# but8LED.net
KiCad netlist of a schematic drawn in EAGLE
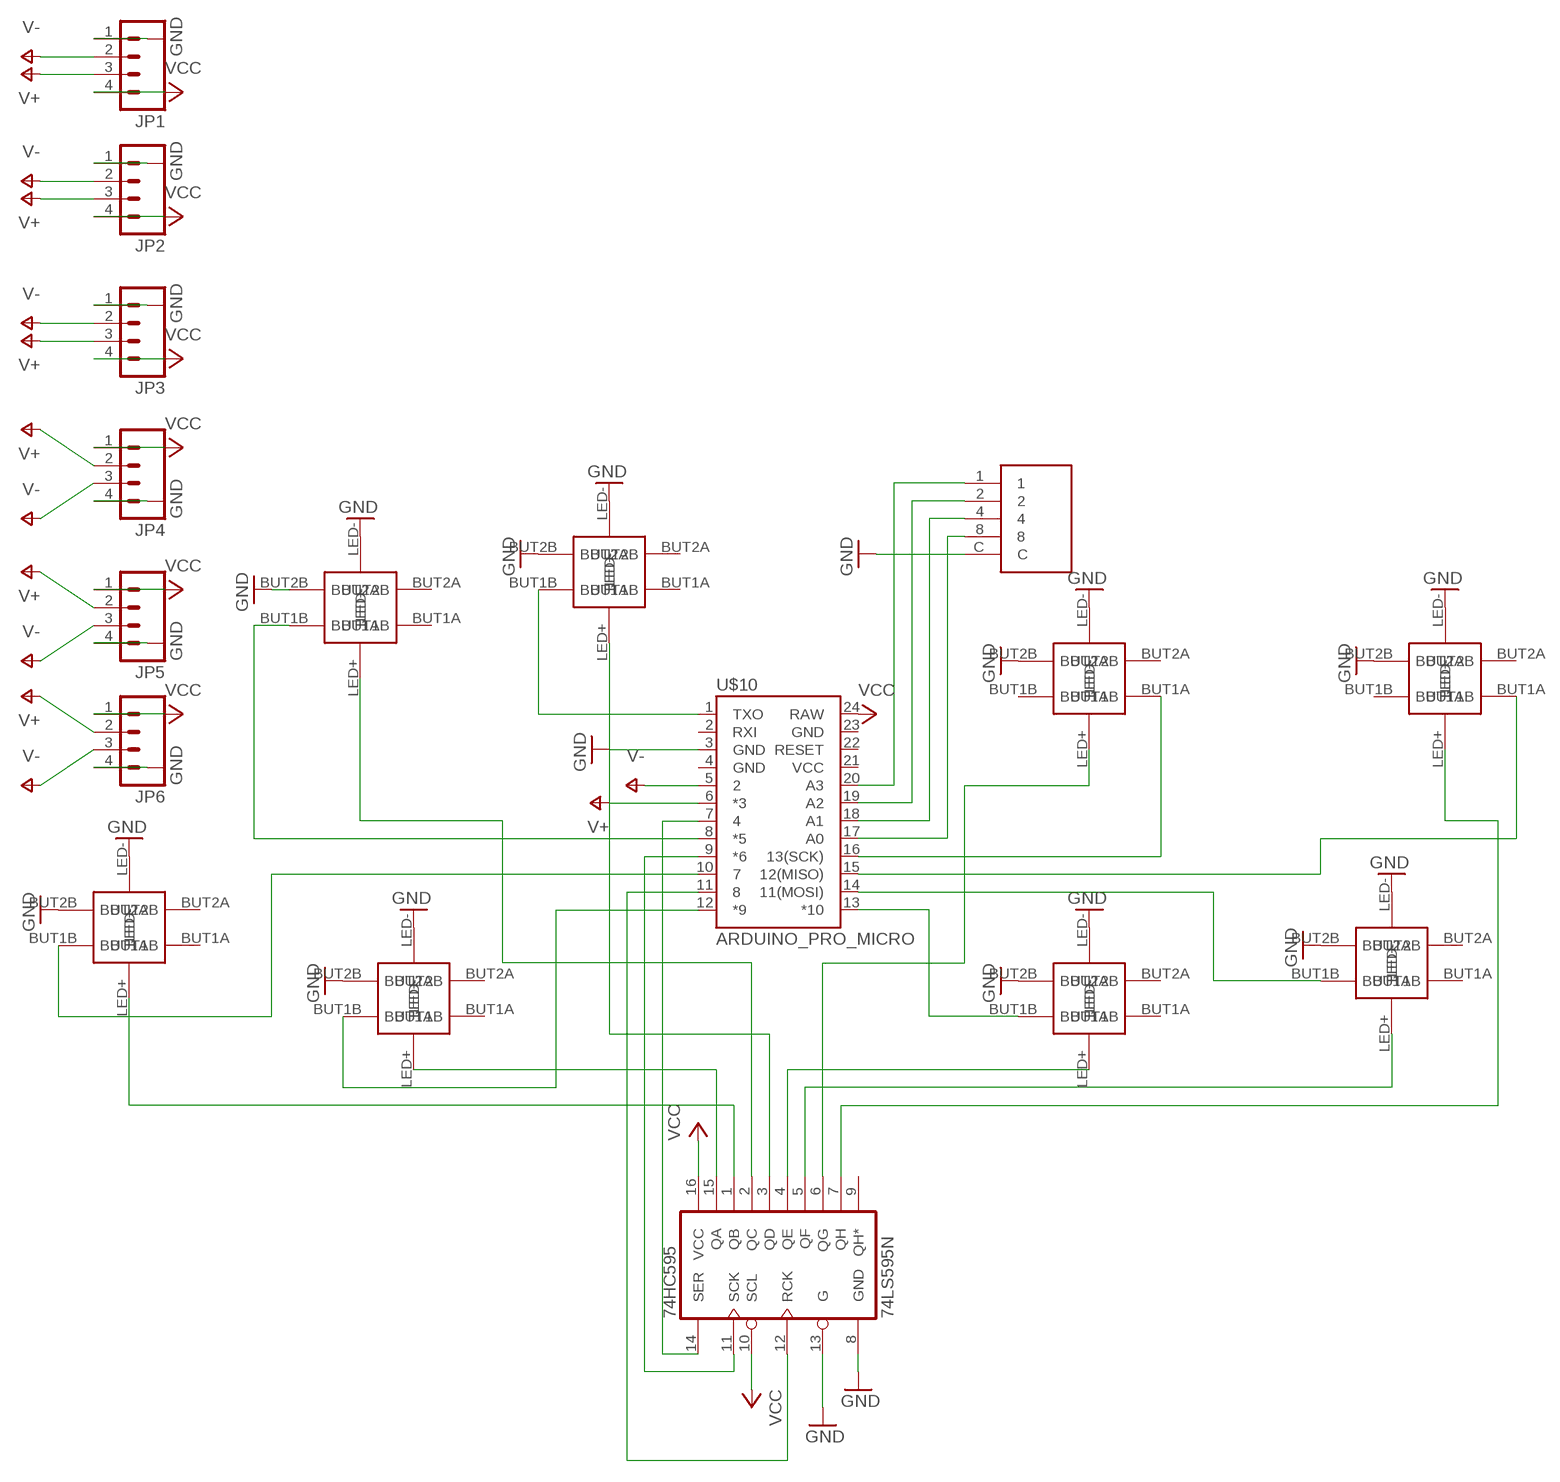
[diagram p0: schematic, sheet 1]

(export (version "E")
  (design (tool "Eeschema 10.0.6"))
  (components
    (comp (ref "74HC595")
      (value "74LS595N")
      (footprint "eagle-import:DIL16")
      (libsource (lib "eagle-import") (part "74595NLS"))
    )
    (comp (ref "JP1")
      (value "M04PTH")
      (footprint "eagle-import:1X04")
      (libsource (lib "eagle-import") (part "M04PTH"))
    )
    (comp (ref "JP2")
      (value "M04PTH")
      (footprint "eagle-import:1X04")
      (libsource (lib "eagle-import") (part "M04PTH"))
    )
    (comp (ref "JP3")
      (value "M04PTH")
      (footprint "eagle-import:1X04")
      (libsource (lib "eagle-import") (part "M04PTH"))
    )
    (comp (ref "JP4")
      (value "M04PTH")
      (footprint "eagle-import:1X04")
      (libsource (lib "eagle-import") (part "M04PTH"))
    )
    (comp (ref "JP5")
      (value "M04PTH")
      (footprint "eagle-import:1X04")
      (libsource (lib "eagle-import") (part "M04PTH"))
    )
    (comp (ref "JP6")
      (value "M04PTH")
      (footprint "eagle-import:1X04")
      (libsource (lib "eagle-import") (part "M04PTH"))
    )
    (comp (ref "U$1")
      (value "BUTLED")
      (footprint "eagle-import:LEDBUT")
      (libsource (lib "eagle-import") (part "BUTLED"))
    )
    (comp (ref "U$2")
      (value "BUTLED")
      (footprint "eagle-import:LEDBUT")
      (libsource (lib "eagle-import") (part "BUTLED"))
    )
    (comp (ref "U$3")
      (value "BUTLED")
      (footprint "eagle-import:LEDBUT")
      (libsource (lib "eagle-import") (part "BUTLED"))
    )
    (comp (ref "U$4")
      (value "BUTLED")
      (footprint "eagle-import:LEDBUT")
      (libsource (lib "eagle-import") (part "BUTLED"))
    )
    (comp (ref "U$5")
      (value "BUTLED")
      (footprint "eagle-import:LEDBUT")
      (libsource (lib "eagle-import") (part "BUTLED"))
    )
    (comp (ref "U$6")
      (value "BUTLED")
      (footprint "eagle-import:LEDBUT")
      (libsource (lib "eagle-import") (part "BUTLED"))
    )
    (comp (ref "U$7")
      (value "BUTLED")
      (footprint "eagle-import:LEDBUT")
      (libsource (lib "eagle-import") (part "BUTLED"))
    )
    (comp (ref "U$8")
      (value "BUTLED")
      (footprint "eagle-import:LEDBUT")
      (libsource (lib "eagle-import") (part "BUTLED"))
    )
    (comp (ref "U$9")
      (value "SWITCH16POS")
      (footprint "eagle-import:SWITCH16POS")
      (libsource (lib "eagle-import") (part "SWITCH16POS"))
    )
    (comp (ref "U$10")
      (value "ARDUINO_PRO_MICRO")
      (footprint "eagle-import:ARDUINO_PRO_MICRO")
      (libsource (lib "eagle-import") (part "ARDUINO_PRO_MICRO"))
    )
  )
  (nets
    (net (code "1") (name "GND") (class "Default")
      (node (ref "74HC595") (pin "13") (pinfunction "G_13") (pintype "input"))
      (node (ref "74HC595") (pin "8") (pinfunction "GND_8") (pintype "power_in"))
      (node (ref "JP1") (pin "1") (pinfunction "1_1") (pintype "passive"))
      (node (ref "JP2") (pin "1") (pinfunction "1_1") (pintype "passive"))
      (node (ref "JP3") (pin "1") (pinfunction "1_1") (pintype "passive"))
      (node (ref "JP4") (pin "4") (pinfunction "4_4") (pintype "passive"))
      (node (ref "JP5") (pin "4") (pinfunction "4_4") (pintype "passive"))
      (node (ref "JP6") (pin "4") (pinfunction "4_4") (pintype "passive"))
      (node (ref "U$1") (pin "BUT2B") (pinfunction "BUT2B_BUT2B") (pintype "bidirectional"))
      (node (ref "U$1") (pin "LED-") (pinfunction "LED-_LED-") (pintype "bidirectional"))
      (node (ref "U$10") (pin "3") (pinfunction "GND_3") (pintype "bidirectional"))
      (node (ref "U$2") (pin "BUT2B") (pinfunction "BUT2B_BUT2B") (pintype "bidirectional"))
      (node (ref "U$2") (pin "LED-") (pinfunction "LED-_LED-") (pintype "bidirectional"))
      (node (ref "U$3") (pin "BUT2B") (pinfunction "BUT2B_BUT2B") (pintype "bidirectional"))
      (node (ref "U$3") (pin "LED-") (pinfunction "LED-_LED-") (pintype "bidirectional"))
      (node (ref "U$4") (pin "BUT2B") (pinfunction "BUT2B_BUT2B") (pintype "bidirectional"))
      (node (ref "U$4") (pin "LED-") (pinfunction "LED-_LED-") (pintype "bidirectional"))
      (node (ref "U$5") (pin "BUT2B") (pinfunction "BUT2B_BUT2B") (pintype "bidirectional"))
      (node (ref "U$5") (pin "LED-") (pinfunction "LED-_LED-") (pintype "bidirectional"))
      (node (ref "U$6") (pin "BUT2B") (pinfunction "BUT2B_BUT2B") (pintype "bidirectional"))
      (node (ref "U$6") (pin "LED-") (pinfunction "LED-_LED-") (pintype "bidirectional"))
      (node (ref "U$7") (pin "BUT2B") (pinfunction "BUT2B_BUT2B") (pintype "bidirectional"))
      (node (ref "U$7") (pin "LED-") (pinfunction "LED-_LED-") (pintype "bidirectional"))
      (node (ref "U$8") (pin "BUT2B") (pinfunction "BUT2B_BUT2B") (pintype "bidirectional"))
      (node (ref "U$8") (pin "LED-") (pinfunction "LED-_LED-") (pintype "bidirectional"))
      (node (ref "U$9") (pin "C") (pinfunction "C_C") (pintype "bidirectional"))
    )
    (net (code "2") (name "Net-(74HC595-QA)") (class "Default")
      (node (ref "74HC595") (pin "15") (pinfunction "QA_15") (pintype "tri_state"))
      (node (ref "U$5") (pin "LED+") (pinfunction "LED+_LED+") (pintype "bidirectional"))
    )
    (net (code "3") (name "Net-(74HC595-QB)") (class "Default")
      (node (ref "74HC595") (pin "1") (pinfunction "QB_1") (pintype "tri_state"))
      (node (ref "U$6") (pin "LED+") (pinfunction "LED+_LED+") (pintype "bidirectional"))
    )
    (net (code "4") (name "Net-(74HC595-QC)") (class "Default")
      (node (ref "74HC595") (pin "2") (pinfunction "QC_2") (pintype "tri_state"))
      (node (ref "U$1") (pin "LED+") (pinfunction "LED+_LED+") (pintype "bidirectional"))
    )
    (net (code "5") (name "Net-(74HC595-QD)") (class "Default")
      (node (ref "74HC595") (pin "3") (pinfunction "QD_3") (pintype "tri_state"))
      (node (ref "U$2") (pin "LED+") (pinfunction "LED+_LED+") (pintype "bidirectional"))
    )
    (net (code "6") (name "Net-(74HC595-QE)") (class "Default")
      (node (ref "74HC595") (pin "4") (pinfunction "QE_4") (pintype "tri_state"))
      (node (ref "U$7") (pin "LED+") (pinfunction "LED+_LED+") (pintype "bidirectional"))
    )
    (net (code "7") (name "Net-(74HC595-QF)") (class "Default")
      (node (ref "74HC595") (pin "5") (pinfunction "QF_5") (pintype "tri_state"))
      (node (ref "U$8") (pin "LED+") (pinfunction "LED+_LED+") (pintype "bidirectional"))
    )
    (net (code "8") (name "Net-(74HC595-QG)") (class "Default")
      (node (ref "74HC595") (pin "6") (pinfunction "QG_6") (pintype "tri_state"))
      (node (ref "U$3") (pin "LED+") (pinfunction "LED+_LED+") (pintype "bidirectional"))
    )
    (net (code "9") (name "Net-(74HC595-QH)") (class "Default")
      (node (ref "74HC595") (pin "7") (pinfunction "QH_7") (pintype "tri_state"))
      (node (ref "U$4") (pin "LED+") (pinfunction "LED+_LED+") (pintype "bidirectional"))
    )
    (net (code "10") (name "Net-(74HC595-RCK)") (class "Default")
      (node (ref "74HC595") (pin "12") (pinfunction "RCK_12") (pintype "input"))
      (node (ref "U$10") (pin "11") (pinfunction "8_11") (pintype "bidirectional"))
    )
    (net (code "11") (name "Net-(74HC595-SCK)") (class "Default")
      (node (ref "74HC595") (pin "11") (pinfunction "SCK_11") (pintype "input"))
      (node (ref "U$10") (pin "9") (pinfunction "*6_9") (pintype "bidirectional"))
    )
    (net (code "12") (name "Net-(74HC595-SER)") (class "Default")
      (node (ref "74HC595") (pin "14") (pinfunction "SER_14") (pintype "input"))
      (node (ref "U$10") (pin "7") (pinfunction "4_7") (pintype "bidirectional"))
    )
    (net (code "13") (name "Net-(U$10-*5)") (class "Default")
      (node (ref "U$1") (pin "BUT1B") (pinfunction "BUT1B_BUT1B") (pintype "bidirectional"))
      (node (ref "U$10") (pin "8") (pinfunction "*5_8") (pintype "bidirectional"))
    )
    (net (code "14") (name "Net-(U$10-*9)") (class "Default")
      (node (ref "U$10") (pin "12") (pinfunction "*9_12") (pintype "bidirectional"))
      (node (ref "U$5") (pin "BUT1B") (pinfunction "BUT1B_BUT1B") (pintype "bidirectional"))
    )
    (net (code "15") (name "Net-(U$10-*10)") (class "Default")
      (node (ref "U$10") (pin "13") (pinfunction "*10_13") (pintype "bidirectional"))
      (node (ref "U$7") (pin "BUT1B") (pinfunction "BUT1B_BUT1B") (pintype "bidirectional"))
    )
    (net (code "16") (name "Net-(U$10-7)") (class "Default")
      (node (ref "U$10") (pin "10") (pinfunction "7_10") (pintype "bidirectional"))
      (node (ref "U$6") (pin "BUT1B") (pinfunction "BUT1B_BUT1B") (pintype "bidirectional"))
    )
    (net (code "17") (name "Net-(U$10-11(MOSI))") (class "Default")
      (node (ref "U$10") (pin "14") (pinfunction "11(MOSI)_14") (pintype "bidirectional"))
      (node (ref "U$8") (pin "BUT1B") (pinfunction "BUT1B_BUT1B") (pintype "bidirectional"))
    )
    (net (code "18") (name "Net-(U$10-12(MISO))") (class "Default")
      (node (ref "U$10") (pin "15") (pinfunction "12(MISO)_15") (pintype "bidirectional"))
      (node (ref "U$4") (pin "BUT1A") (pinfunction "BUT1A_BUT1A") (pintype "bidirectional"))
    )
    (net (code "19") (name "Net-(U$10-13(SCK))") (class "Default")
      (node (ref "U$10") (pin "16") (pinfunction "13(SCK)_16") (pintype "bidirectional"))
      (node (ref "U$3") (pin "BUT1A") (pinfunction "BUT1A_BUT1A") (pintype "bidirectional"))
    )
    (net (code "20") (name "Net-(U$10-A0)") (class "Default")
      (node (ref "U$10") (pin "17") (pinfunction "A0_17") (pintype "bidirectional"))
      (node (ref "U$9") (pin "8") (pinfunction "8_8") (pintype "bidirectional"))
    )
    (net (code "21") (name "Net-(U$10-A1)") (class "Default")
      (node (ref "U$10") (pin "18") (pinfunction "A1_18") (pintype "bidirectional"))
      (node (ref "U$9") (pin "4") (pinfunction "4_4") (pintype "bidirectional"))
    )
    (net (code "22") (name "Net-(U$10-A2)") (class "Default")
      (node (ref "U$10") (pin "19") (pinfunction "A2_19") (pintype "bidirectional"))
      (node (ref "U$9") (pin "2") (pinfunction "2_2") (pintype "bidirectional"))
    )
    (net (code "23") (name "Net-(U$10-A3)") (class "Default")
      (node (ref "U$10") (pin "20") (pinfunction "A3_20") (pintype "bidirectional"))
      (node (ref "U$9") (pin "1") (pinfunction "1_1") (pintype "bidirectional"))
    )
    (net (code "24") (name "Net-(U$10-TXO)") (class "Default")
      (node (ref "U$10") (pin "1") (pinfunction "TXO_1") (pintype "bidirectional"))
      (node (ref "U$2") (pin "BUT1B") (pinfunction "BUT1B_BUT1B") (pintype "bidirectional"))
    )
    (net (code "25") (name "V+") (class "Default")
      (node (ref "JP1") (pin "3") (pinfunction "3_3") (pintype "passive"))
      (node (ref "JP2") (pin "3") (pinfunction "3_3") (pintype "passive"))
      (node (ref "JP3") (pin "3") (pinfunction "3_3") (pintype "passive"))
      (node (ref "JP4") (pin "2") (pinfunction "2_2") (pintype "passive"))
      (node (ref "JP5") (pin "2") (pinfunction "2_2") (pintype "passive"))
      (node (ref "JP6") (pin "2") (pinfunction "2_2") (pintype "passive"))
      (node (ref "U$10") (pin "6") (pinfunction "*3_6") (pintype "bidirectional"))
    )
    (net (code "26") (name "V-") (class "Default")
      (node (ref "JP1") (pin "2") (pinfunction "2_2") (pintype "passive"))
      (node (ref "JP2") (pin "2") (pinfunction "2_2") (pintype "passive"))
      (node (ref "JP3") (pin "2") (pinfunction "2_2") (pintype "passive"))
      (node (ref "JP4") (pin "3") (pinfunction "3_3") (pintype "passive"))
      (node (ref "JP5") (pin "3") (pinfunction "3_3") (pintype "passive"))
      (node (ref "JP6") (pin "3") (pinfunction "3_3") (pintype "passive"))
      (node (ref "U$10") (pin "5") (pinfunction "2_5") (pintype "bidirectional"))
    )
    (net (code "27") (name "VCC") (class "Default")
      (node (ref "74HC595") (pin "10") (pinfunction "SCL_10") (pintype "input"))
      (node (ref "74HC595") (pin "16") (pinfunction "VCC_16") (pintype "power_in"))
      (node (ref "JP1") (pin "4") (pinfunction "4_4") (pintype "passive"))
      (node (ref "JP2") (pin "4") (pinfunction "4_4") (pintype "passive"))
      (node (ref "JP3") (pin "4") (pinfunction "4_4") (pintype "passive"))
      (node (ref "JP4") (pin "1") (pinfunction "1_1") (pintype "passive"))
      (node (ref "JP5") (pin "1") (pinfunction "1_1") (pintype "passive"))
      (node (ref "JP6") (pin "1") (pinfunction "1_1") (pintype "passive"))
      (node (ref "U$10") (pin "24") (pinfunction "RAW_24") (pintype "bidirectional"))
    )
    (net (code "28") (name "unconnected-(74HC595-QH*-Pad9)") (class "Default")
      (node (ref "74HC595") (pin "9") (pinfunction "QH*_9") (pintype "tri_state"))
    )
    (net (code "29") (name "unconnected-(U$1-PadBUT1A)") (class "Default")
      (node (ref "U$1") (pin "BUT1A") (pinfunction "BUT1A_BUT1A") (pintype "bidirectional"))
    )
    (net (code "30") (name "unconnected-(U$1-PadBUT2A)") (class "Default")
      (node (ref "U$1") (pin "BUT2A") (pinfunction "BUT2A_BUT2A") (pintype "bidirectional"))
    )
    (net (code "31") (name "unconnected-(U$2-PadBUT1A)") (class "Default")
      (node (ref "U$2") (pin "BUT1A") (pinfunction "BUT1A_BUT1A") (pintype "bidirectional"))
    )
    (net (code "32") (name "unconnected-(U$2-PadBUT2A)") (class "Default")
      (node (ref "U$2") (pin "BUT2A") (pinfunction "BUT2A_BUT2A") (pintype "bidirectional"))
    )
    (net (code "33") (name "unconnected-(U$3-PadBUT1B)") (class "Default")
      (node (ref "U$3") (pin "BUT1B") (pinfunction "BUT1B_BUT1B") (pintype "bidirectional"))
    )
    (net (code "34") (name "unconnected-(U$3-PadBUT2A)") (class "Default")
      (node (ref "U$3") (pin "BUT2A") (pinfunction "BUT2A_BUT2A") (pintype "bidirectional"))
    )
    (net (code "35") (name "unconnected-(U$4-PadBUT1B)") (class "Default")
      (node (ref "U$4") (pin "BUT1B") (pinfunction "BUT1B_BUT1B") (pintype "bidirectional"))
    )
    (net (code "36") (name "unconnected-(U$4-PadBUT2A)") (class "Default")
      (node (ref "U$4") (pin "BUT2A") (pinfunction "BUT2A_BUT2A") (pintype "bidirectional"))
    )
    (net (code "37") (name "unconnected-(U$5-PadBUT1A)") (class "Default")
      (node (ref "U$5") (pin "BUT1A") (pinfunction "BUT1A_BUT1A") (pintype "bidirectional"))
    )
    (net (code "38") (name "unconnected-(U$5-PadBUT2A)") (class "Default")
      (node (ref "U$5") (pin "BUT2A") (pinfunction "BUT2A_BUT2A") (pintype "bidirectional"))
    )
    (net (code "39") (name "unconnected-(U$6-PadBUT1A)") (class "Default")
      (node (ref "U$6") (pin "BUT1A") (pinfunction "BUT1A_BUT1A") (pintype "bidirectional"))
    )
    (net (code "40") (name "unconnected-(U$6-PadBUT2A)") (class "Default")
      (node (ref "U$6") (pin "BUT2A") (pinfunction "BUT2A_BUT2A") (pintype "bidirectional"))
    )
    (net (code "41") (name "unconnected-(U$7-PadBUT1A)") (class "Default")
      (node (ref "U$7") (pin "BUT1A") (pinfunction "BUT1A_BUT1A") (pintype "bidirectional"))
    )
    (net (code "42") (name "unconnected-(U$7-PadBUT2A)") (class "Default")
      (node (ref "U$7") (pin "BUT2A") (pinfunction "BUT2A_BUT2A") (pintype "bidirectional"))
    )
    (net (code "43") (name "unconnected-(U$8-PadBUT1A)") (class "Default")
      (node (ref "U$8") (pin "BUT1A") (pinfunction "BUT1A_BUT1A") (pintype "bidirectional"))
    )
    (net (code "44") (name "unconnected-(U$8-PadBUT2A)") (class "Default")
      (node (ref "U$8") (pin "BUT2A") (pinfunction "BUT2A_BUT2A") (pintype "bidirectional"))
    )
    (net (code "45") (name "unconnected-(U$10-GND-Pad4)") (class "Default")
      (node (ref "U$10") (pin "4") (pinfunction "GND_4") (pintype "bidirectional"))
    )
    (net (code "46") (name "unconnected-(U$10-GND-Pad23)") (class "Default")
      (node (ref "U$10") (pin "23") (pinfunction "GND_23") (pintype "bidirectional"))
    )
    (net (code "47") (name "unconnected-(U$10-RESET-Pad22)") (class "Default")
      (node (ref "U$10") (pin "22") (pinfunction "RESET_22") (pintype "bidirectional"))
    )
    (net (code "48") (name "unconnected-(U$10-RXI-Pad2)") (class "Default")
      (node (ref "U$10") (pin "2") (pinfunction "RXI_2") (pintype "bidirectional"))
    )
    (net (code "49") (name "unconnected-(U$10-VCC-Pad21)") (class "Default")
      (node (ref "U$10") (pin "21") (pinfunction "VCC_21") (pintype "bidirectional"))
    )
  )
)
